# GBWand.net
KiCad netlist of a schematic drawn in EAGLE
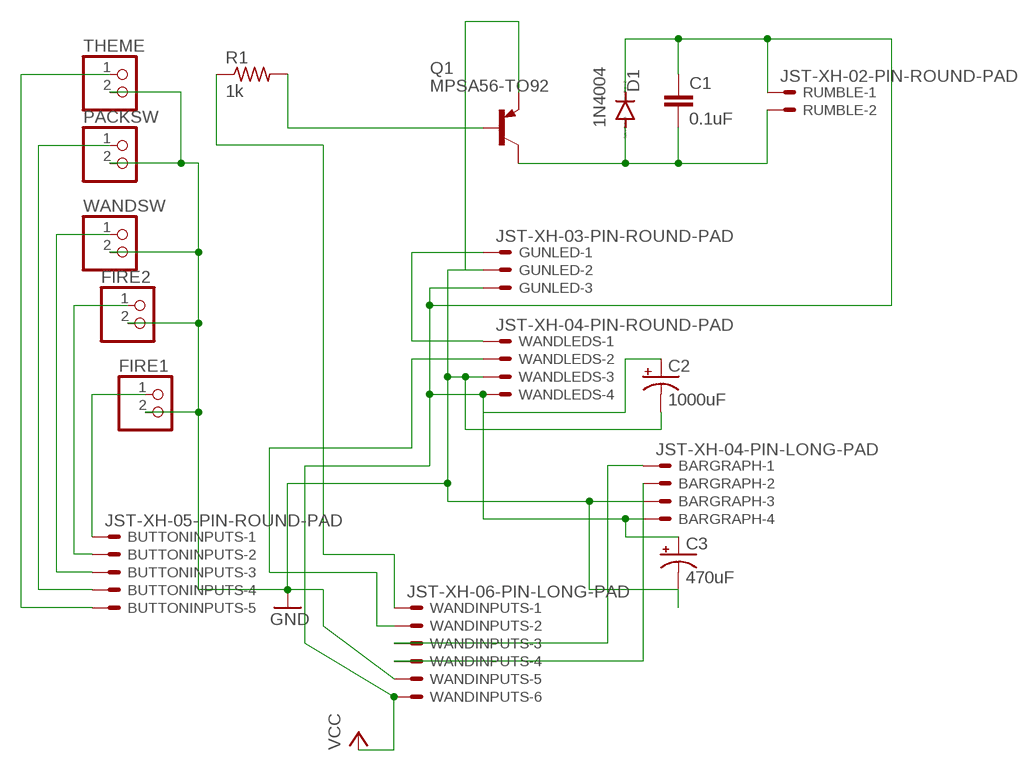
[diagram p0: schematic, sheet 1]

(export (version "E")
  (design (tool "Eeschema 10.0.6"))
  (components
    (comp (ref "BARGRAPH")
      (value "JST-XH-04-PIN-LONG-PAD")
      (footprint "eagle-import:JST-XH-04-PACKAGE-LONG-PAD")
      (libsource (lib "eagle-import") (part "JST-XH-04-PIN-LONG-PAD"))
    )
    (comp (ref "BUTTONINPUTS")
      (value "JST-XH-05-PIN-ROUND-PAD")
      (footprint "eagle-import:JST-XH-05-PACKAGE-ROUND-PAD")
      (libsource (lib "eagle-import") (part "JST-XH-05-PIN-ROUND-PAD"))
    )
    (comp (ref "C1")
      (value "0.1uF")
      (footprint "eagle-import:C050-024X044")
      (libsource (lib "eagle-import") (part "C-EU050-024X044"))
    )
    (comp (ref "C2")
      (value "1000uF")
      (footprint "eagle-import:E2,5-6")
      (libsource (lib "eagle-import") (part "CPOL-USE2.5-6"))
    )
    (comp (ref "C3")
      (value "470uF")
      (footprint "eagle-import:E2,5-6")
      (libsource (lib "eagle-import") (part "CPOL-USE2.5-6"))
    )
    (comp (ref "D1")
      (value "1N4004")
      (footprint "eagle-import:DO41-10")
      (libsource (lib "eagle-import") (part "1N4004"))
    )
    (comp (ref "FIRE1")
      (value "PINHD-1X2")
      (footprint "eagle-import:1X02")
      (libsource (lib "eagle-import") (part "PINHD-1X2"))
    )
    (comp (ref "FIRE2")
      (value "PINHD-1X2")
      (footprint "eagle-import:1X02")
      (libsource (lib "eagle-import") (part "PINHD-1X2"))
    )
    (comp (ref "GUNLED")
      (value "JST-XH-03-PIN-ROUND-PAD")
      (footprint "eagle-import:JST-XH-03-PACKAGE-ROUND-PAD")
      (libsource (lib "eagle-import") (part "JST-XH-03-PIN-ROUND-PAD"))
    )
    (comp (ref "PACKSW")
      (value "PINHD-1X2")
      (footprint "eagle-import:1X02")
      (libsource (lib "eagle-import") (part "PINHD-1X2"))
    )
    (comp (ref "Q1")
      (value "MPSA56-TO92")
      (footprint "eagle-import:TO92-CBE")
      (libsource (lib "eagle-import") (part "-?TO92MPSA56"))
    )
    (comp (ref "R1")
      (value "1k")
      (footprint "eagle-import:0207_9")
      (libsource (lib "eagle-import") (part "R-US_0207/9"))
    )
    (comp (ref "RUMBLE")
      (value "JST-XH-02-PIN-ROUND-PAD")
      (footprint "eagle-import:JST-XH-02-PACKAGE-ROUND-PAD")
      (libsource (lib "eagle-import") (part "JST-XH-02-PIN-ROUND-PAD"))
    )
    (comp (ref "THEME")
      (value "PINHD-1X2")
      (footprint "eagle-import:1X02")
      (libsource (lib "eagle-import") (part "PINHD-1X2"))
    )
    (comp (ref "WANDINPUTS")
      (value "JST-XH-06-PIN-LONG-PAD")
      (footprint "eagle-import:JST-XH-06-PACKAGE-LONG-PAD")
      (libsource (lib "eagle-import") (part "JST-XH-06-PIN-LONG-PAD"))
    )
    (comp (ref "WANDLEDS")
      (value "JST-XH-04-PIN-ROUND-PAD")
      (footprint "eagle-import:JST-XH-04-PACKAGE-ROUND-PAD")
      (libsource (lib "eagle-import") (part "JST-XH-04-PIN-ROUND-PAD"))
    )
    (comp (ref "WANDSW")
      (value "PINHD-1X2")
      (footprint "eagle-import:1X02")
      (libsource (lib "eagle-import") (part "PINHD-1X2"))
    )
  )
  (nets
    (net (code "1") (name "GND") (class "Default")
      (node (ref "BARGRAPH") (pin "3") (pinfunction "S_3") (pintype "passive"))
      (node (ref "C2") (pin "-") (pinfunction "-_-") (pintype "passive"))
      (node (ref "C3") (pin "-") (pinfunction "-_-") (pintype "passive"))
      (node (ref "FIRE1") (pin "2") (pinfunction "2_2") (pintype "passive"))
      (node (ref "FIRE2") (pin "2") (pinfunction "2_2") (pintype "passive"))
      (node (ref "GUNLED") (pin "2") (pinfunction "S_2") (pintype "passive"))
      (node (ref "PACKSW") (pin "2") (pinfunction "2_2") (pintype "passive"))
      (node (ref "Q1") (pin "E") (pinfunction "E_E") (pintype "passive"))
      (node (ref "THEME") (pin "2") (pinfunction "2_2") (pintype "passive"))
      (node (ref "WANDINPUTS") (pin "5") (pinfunction "S_5") (pintype "passive"))
      (node (ref "WANDLEDS") (pin "3") (pinfunction "S_3") (pintype "passive"))
      (node (ref "WANDSW") (pin "2") (pinfunction "2_2") (pintype "passive"))
    )
    (net (code "2") (name "Net-(BARGRAPHA-S)") (class "Default")
      (node (ref "BARGRAPH") (pin "1") (pinfunction "S_1") (pintype "passive"))
      (node (ref "WANDINPUTS") (pin "3") (pinfunction "S_3") (pintype "passive"))
    )
    (net (code "3") (name "Net-(BARGRAPHB-S)") (class "Default")
      (node (ref "BARGRAPH") (pin "2") (pinfunction "S_2") (pintype "passive"))
      (node (ref "WANDINPUTS") (pin "4") (pinfunction "S_4") (pintype "passive"))
    )
    (net (code "4") (name "Net-(BUTTONINPUTSA-S)") (class "Default")
      (node (ref "BUTTONINPUTS") (pin "1") (pinfunction "S_1") (pintype "passive"))
      (node (ref "FIRE1") (pin "1") (pinfunction "1_1") (pintype "passive"))
    )
    (net (code "5") (name "Net-(BUTTONINPUTSB-S)") (class "Default")
      (node (ref "BUTTONINPUTS") (pin "2") (pinfunction "S_2") (pintype "passive"))
      (node (ref "FIRE2") (pin "1") (pinfunction "1_1") (pintype "passive"))
    )
    (net (code "6") (name "Net-(BUTTONINPUTSC-S)") (class "Default")
      (node (ref "BUTTONINPUTS") (pin "3") (pinfunction "S_3") (pintype "passive"))
      (node (ref "WANDSW") (pin "1") (pinfunction "1_1") (pintype "passive"))
    )
    (net (code "7") (name "Net-(BUTTONINPUTSD-S)") (class "Default")
      (node (ref "BUTTONINPUTS") (pin "4") (pinfunction "S_4") (pintype "passive"))
      (node (ref "PACKSW") (pin "1") (pinfunction "1_1") (pintype "passive"))
    )
    (net (code "8") (name "Net-(BUTTONINPUTSE-S)") (class "Default")
      (node (ref "BUTTONINPUTS") (pin "5") (pinfunction "S_5") (pintype "passive"))
      (node (ref "THEME") (pin "1") (pinfunction "1_1") (pintype "passive"))
    )
    (net (code "9") (name "Net-(GUNLEDA-S)") (class "Default")
      (node (ref "GUNLED") (pin "1") (pinfunction "S_1") (pintype "passive"))
      (node (ref "WANDLEDS") (pin "1") (pinfunction "S_1") (pintype "passive"))
    )
    (net (code "10") (name "Net-(Q1-PadB)") (class "Default")
      (node (ref "Q1") (pin "B") (pinfunction "B_B") (pintype "passive"))
      (node (ref "R1") (pin "2") (pinfunction "2_2") (pintype "passive"))
    )
    (net (code "11") (name "Net-(RUMBLEB-S)") (class "Default")
      (node (ref "C1") (pin "2") (pinfunction "2_2") (pintype "passive"))
      (node (ref "D1") (pin "A") (pinfunction "A_A") (pintype "passive"))
      (node (ref "Q1") (pin "C") (pinfunction "C_C") (pintype "passive"))
      (node (ref "RUMBLE") (pin "2") (pinfunction "S_2") (pintype "passive"))
    )
    (net (code "12") (name "Net-(WANDINPUTSA-S)") (class "Default")
      (node (ref "R1") (pin "1") (pinfunction "1_1") (pintype "passive"))
      (node (ref "WANDINPUTS") (pin "1") (pinfunction "S_1") (pintype "passive"))
    )
    (net (code "13") (name "Net-(WANDINPUTSB-S)") (class "Default")
      (node (ref "WANDINPUTS") (pin "2") (pinfunction "S_2") (pintype "passive"))
      (node (ref "WANDLEDS") (pin "2") (pinfunction "S_2") (pintype "passive"))
    )
    (net (code "14") (name "VCC") (class "Default")
      (node (ref "BARGRAPH") (pin "4") (pinfunction "S_4") (pintype "passive"))
      (node (ref "C1") (pin "1") (pinfunction "1_1") (pintype "passive"))
      (node (ref "C2") (pin "+") (pinfunction "+_+") (pintype "passive"))
      (node (ref "C3") (pin "+") (pinfunction "+_+") (pintype "passive"))
      (node (ref "D1") (pin "C") (pinfunction "C_C") (pintype "passive"))
      (node (ref "GUNLED") (pin "3") (pinfunction "S_3") (pintype "passive"))
      (node (ref "RUMBLE") (pin "1") (pinfunction "S_1") (pintype "passive"))
      (node (ref "WANDINPUTS") (pin "6") (pinfunction "S_6") (pintype "passive"))
      (node (ref "WANDLEDS") (pin "4") (pinfunction "S_4") (pintype "passive"))
    )
  )
)
